# punktschwei__pulser_mosfets.net
KiCad netlist of a schematic drawn in EAGLE
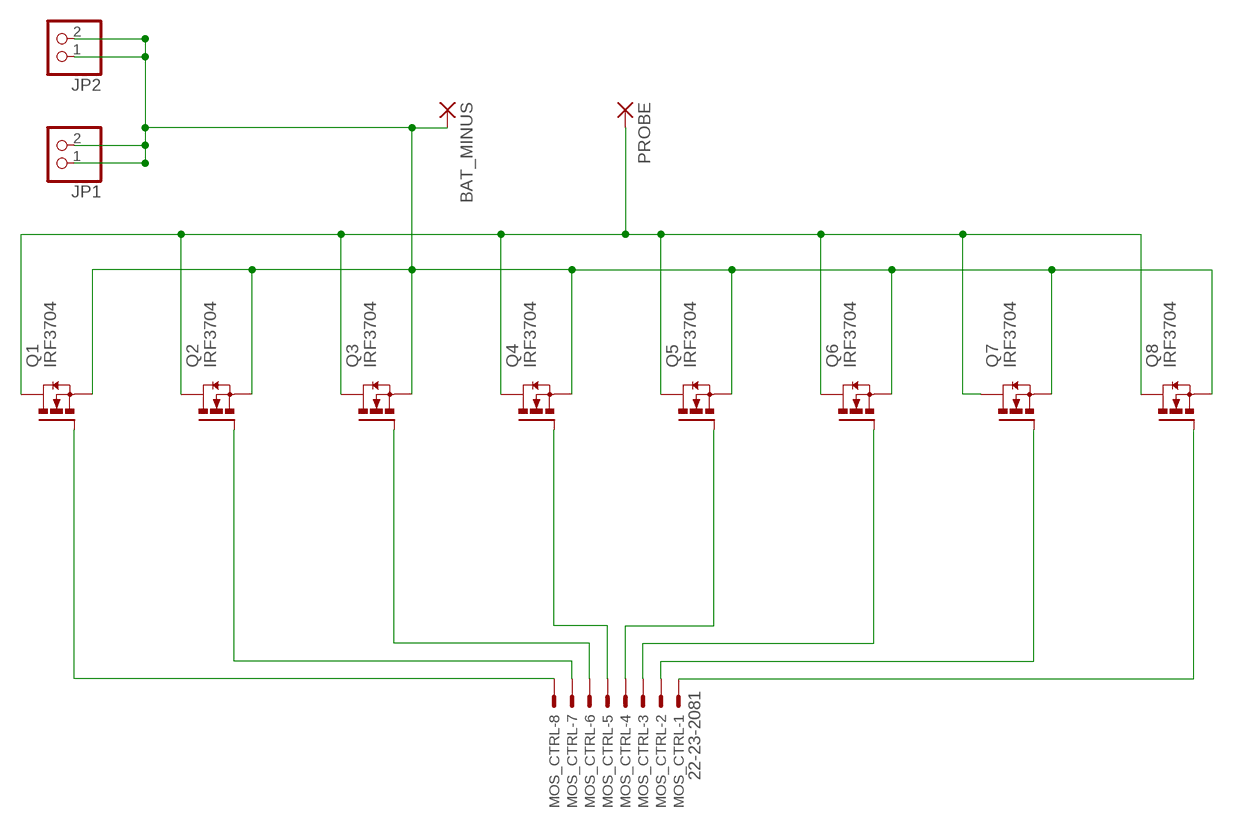
[diagram p0: schematic, sheet 1]

(export (version "E")
  (design (tool "Eeschema 10.0.6"))
  (components
    (comp (ref "BAT_MINUS")
      (value "2,54/0,9")
      (footprint "eagle-import:2,54_0,9")
      (libsource (lib "eagle-import") (part "2,54/0,9"))
    )
    (comp (ref "JP1")
      (value "PINHD-1X2")
      (footprint "eagle-import:1X02")
      (libsource (lib "eagle-import") (part "PINHD-1X2"))
    )
    (comp (ref "JP2")
      (value "PINHD-1X2")
      (footprint "eagle-import:1X02")
      (libsource (lib "eagle-import") (part "PINHD-1X2"))
    )
    (comp (ref "MOS_CTRL")
      (value "22-23-2081")
      (footprint "eagle-import:22-23-2081")
      (fields (field (name "MF") "MOLEX"))
      (libsource (lib "eagle-import") (part "22-23-2081"))
    )
    (comp (ref "PROBE")
      (value "2,54/0,9")
      (footprint "eagle-import:2,54_0,9")
      (libsource (lib "eagle-import") (part "2,54/0,9"))
    )
    (comp (ref "Q1")
      (value "IRF3704")
      (footprint "eagle-import:TO220AH")
      (libsource (lib "eagle-import") (part "IRF3704"))
    )
    (comp (ref "Q2")
      (value "IRF3704")
      (footprint "eagle-import:TO220AH")
      (libsource (lib "eagle-import") (part "IRF3704"))
    )
    (comp (ref "Q3")
      (value "IRF3704")
      (footprint "eagle-import:TO220AH")
      (libsource (lib "eagle-import") (part "IRF3704"))
    )
    (comp (ref "Q4")
      (value "IRF3704")
      (footprint "eagle-import:TO220AH")
      (libsource (lib "eagle-import") (part "IRF3704"))
    )
    (comp (ref "Q5")
      (value "IRF3704")
      (footprint "eagle-import:TO220AH")
      (libsource (lib "eagle-import") (part "IRF3704"))
    )
    (comp (ref "Q6")
      (value "IRF3704")
      (footprint "eagle-import:TO220AH")
      (libsource (lib "eagle-import") (part "IRF3704"))
    )
    (comp (ref "Q7")
      (value "IRF3704")
      (footprint "eagle-import:TO220AH")
      (libsource (lib "eagle-import") (part "IRF3704"))
    )
    (comp (ref "Q8")
      (value "IRF3704")
      (footprint "eagle-import:TO220AH")
      (libsource (lib "eagle-import") (part "IRF3704"))
    )
  )
  (nets
    (net (code "1") (name "Net-(BAT_MINUS-P)") (class "Default")
      (node (ref "BAT_MINUS") (pin "1") (pinfunction "P_1") (pintype "passive"))
      (node (ref "JP1") (pin "1") (pinfunction "1_1") (pintype "passive"))
      (node (ref "JP1") (pin "2") (pinfunction "2_2") (pintype "passive"))
      (node (ref "JP2") (pin "1") (pinfunction "1_1") (pintype "passive"))
      (node (ref "JP2") (pin "2") (pinfunction "2_2") (pintype "passive"))
      (node (ref "Q1") (pin "E") (pinfunction "S_E") (pintype "passive"))
      (node (ref "Q2") (pin "E") (pinfunction "S_E") (pintype "passive"))
      (node (ref "Q3") (pin "E") (pinfunction "S_E") (pintype "passive"))
      (node (ref "Q4") (pin "E") (pinfunction "S_E") (pintype "passive"))
      (node (ref "Q5") (pin "E") (pinfunction "S_E") (pintype "passive"))
      (node (ref "Q6") (pin "E") (pinfunction "S_E") (pintype "passive"))
      (node (ref "Q7") (pin "E") (pinfunction "S_E") (pintype "passive"))
      (node (ref "Q8") (pin "E") (pinfunction "S_E") (pintype "passive"))
    )
    (net (code "2") (name "Net-(MOS_CTRLA-S)") (class "Default")
      (node (ref "MOS_CTRL") (pin "1") (pinfunction "S_1") (pintype "passive"))
      (node (ref "Q8") (pin "B") (pinfunction "G_B") (pintype "passive"))
    )
    (net (code "3") (name "Net-(MOS_CTRLB-S)") (class "Default")
      (node (ref "MOS_CTRL") (pin "2") (pinfunction "S_2") (pintype "passive"))
      (node (ref "Q7") (pin "B") (pinfunction "G_B") (pintype "passive"))
    )
    (net (code "4") (name "Net-(MOS_CTRLC-S)") (class "Default")
      (node (ref "MOS_CTRL") (pin "3") (pinfunction "S_3") (pintype "passive"))
      (node (ref "Q6") (pin "B") (pinfunction "G_B") (pintype "passive"))
    )
    (net (code "5") (name "Net-(MOS_CTRLD-S)") (class "Default")
      (node (ref "MOS_CTRL") (pin "4") (pinfunction "S_4") (pintype "passive"))
      (node (ref "Q5") (pin "B") (pinfunction "G_B") (pintype "passive"))
    )
    (net (code "6") (name "Net-(MOS_CTRLE-S)") (class "Default")
      (node (ref "MOS_CTRL") (pin "5") (pinfunction "S_5") (pintype "passive"))
      (node (ref "Q4") (pin "B") (pinfunction "G_B") (pintype "passive"))
    )
    (net (code "7") (name "Net-(MOS_CTRLF-S)") (class "Default")
      (node (ref "MOS_CTRL") (pin "6") (pinfunction "S_6") (pintype "passive"))
      (node (ref "Q3") (pin "B") (pinfunction "G_B") (pintype "passive"))
    )
    (net (code "8") (name "Net-(MOS_CTRLG-S)") (class "Default")
      (node (ref "MOS_CTRL") (pin "7") (pinfunction "S_7") (pintype "passive"))
      (node (ref "Q2") (pin "B") (pinfunction "G_B") (pintype "passive"))
    )
    (net (code "9") (name "Net-(MOS_CTRLH-S)") (class "Default")
      (node (ref "MOS_CTRL") (pin "8") (pinfunction "S_8") (pintype "passive"))
      (node (ref "Q1") (pin "B") (pinfunction "G_B") (pintype "passive"))
    )
    (net (code "10") (name "Net-(PROBE-P)") (class "Default")
      (node (ref "PROBE") (pin "1") (pinfunction "P_1") (pintype "passive"))
      (node (ref "Q1") (pin "C") (pinfunction "D_C") (pintype "passive"))
      (node (ref "Q2") (pin "C") (pinfunction "D_C") (pintype "passive"))
      (node (ref "Q3") (pin "C") (pinfunction "D_C") (pintype "passive"))
      (node (ref "Q4") (pin "C") (pinfunction "D_C") (pintype "passive"))
      (node (ref "Q5") (pin "C") (pinfunction "D_C") (pintype "passive"))
      (node (ref "Q6") (pin "C") (pinfunction "D_C") (pintype "passive"))
      (node (ref "Q7") (pin "C") (pinfunction "D_C") (pintype "passive"))
      (node (ref "Q8") (pin "C") (pinfunction "D_C") (pintype "passive"))
    )
  )
)
